# CH32M030C8T7_1V3.net
KiCad netlist of a schematic drawn in Altium Designer
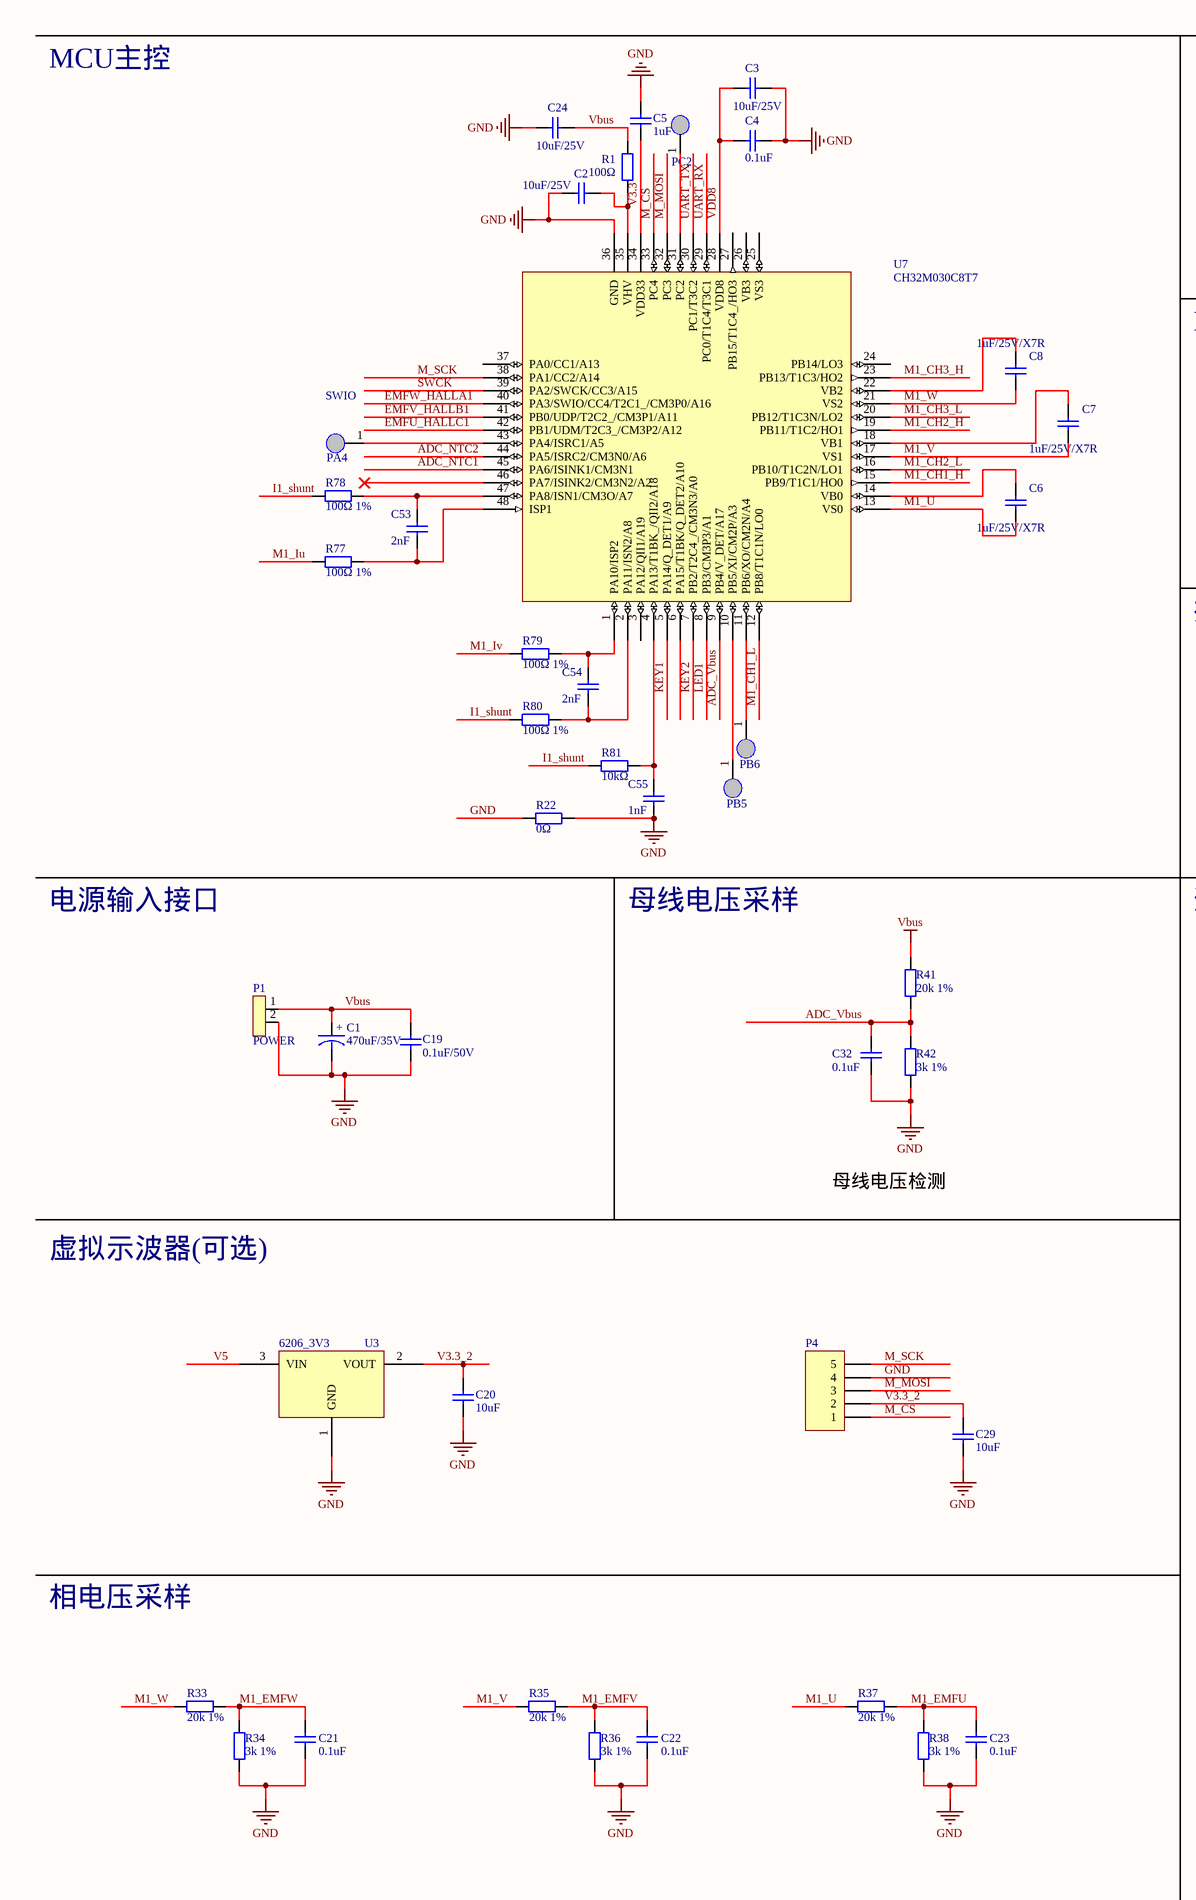
[diagram p0: CH32M030C8T7_1V3.SchDoc, left]
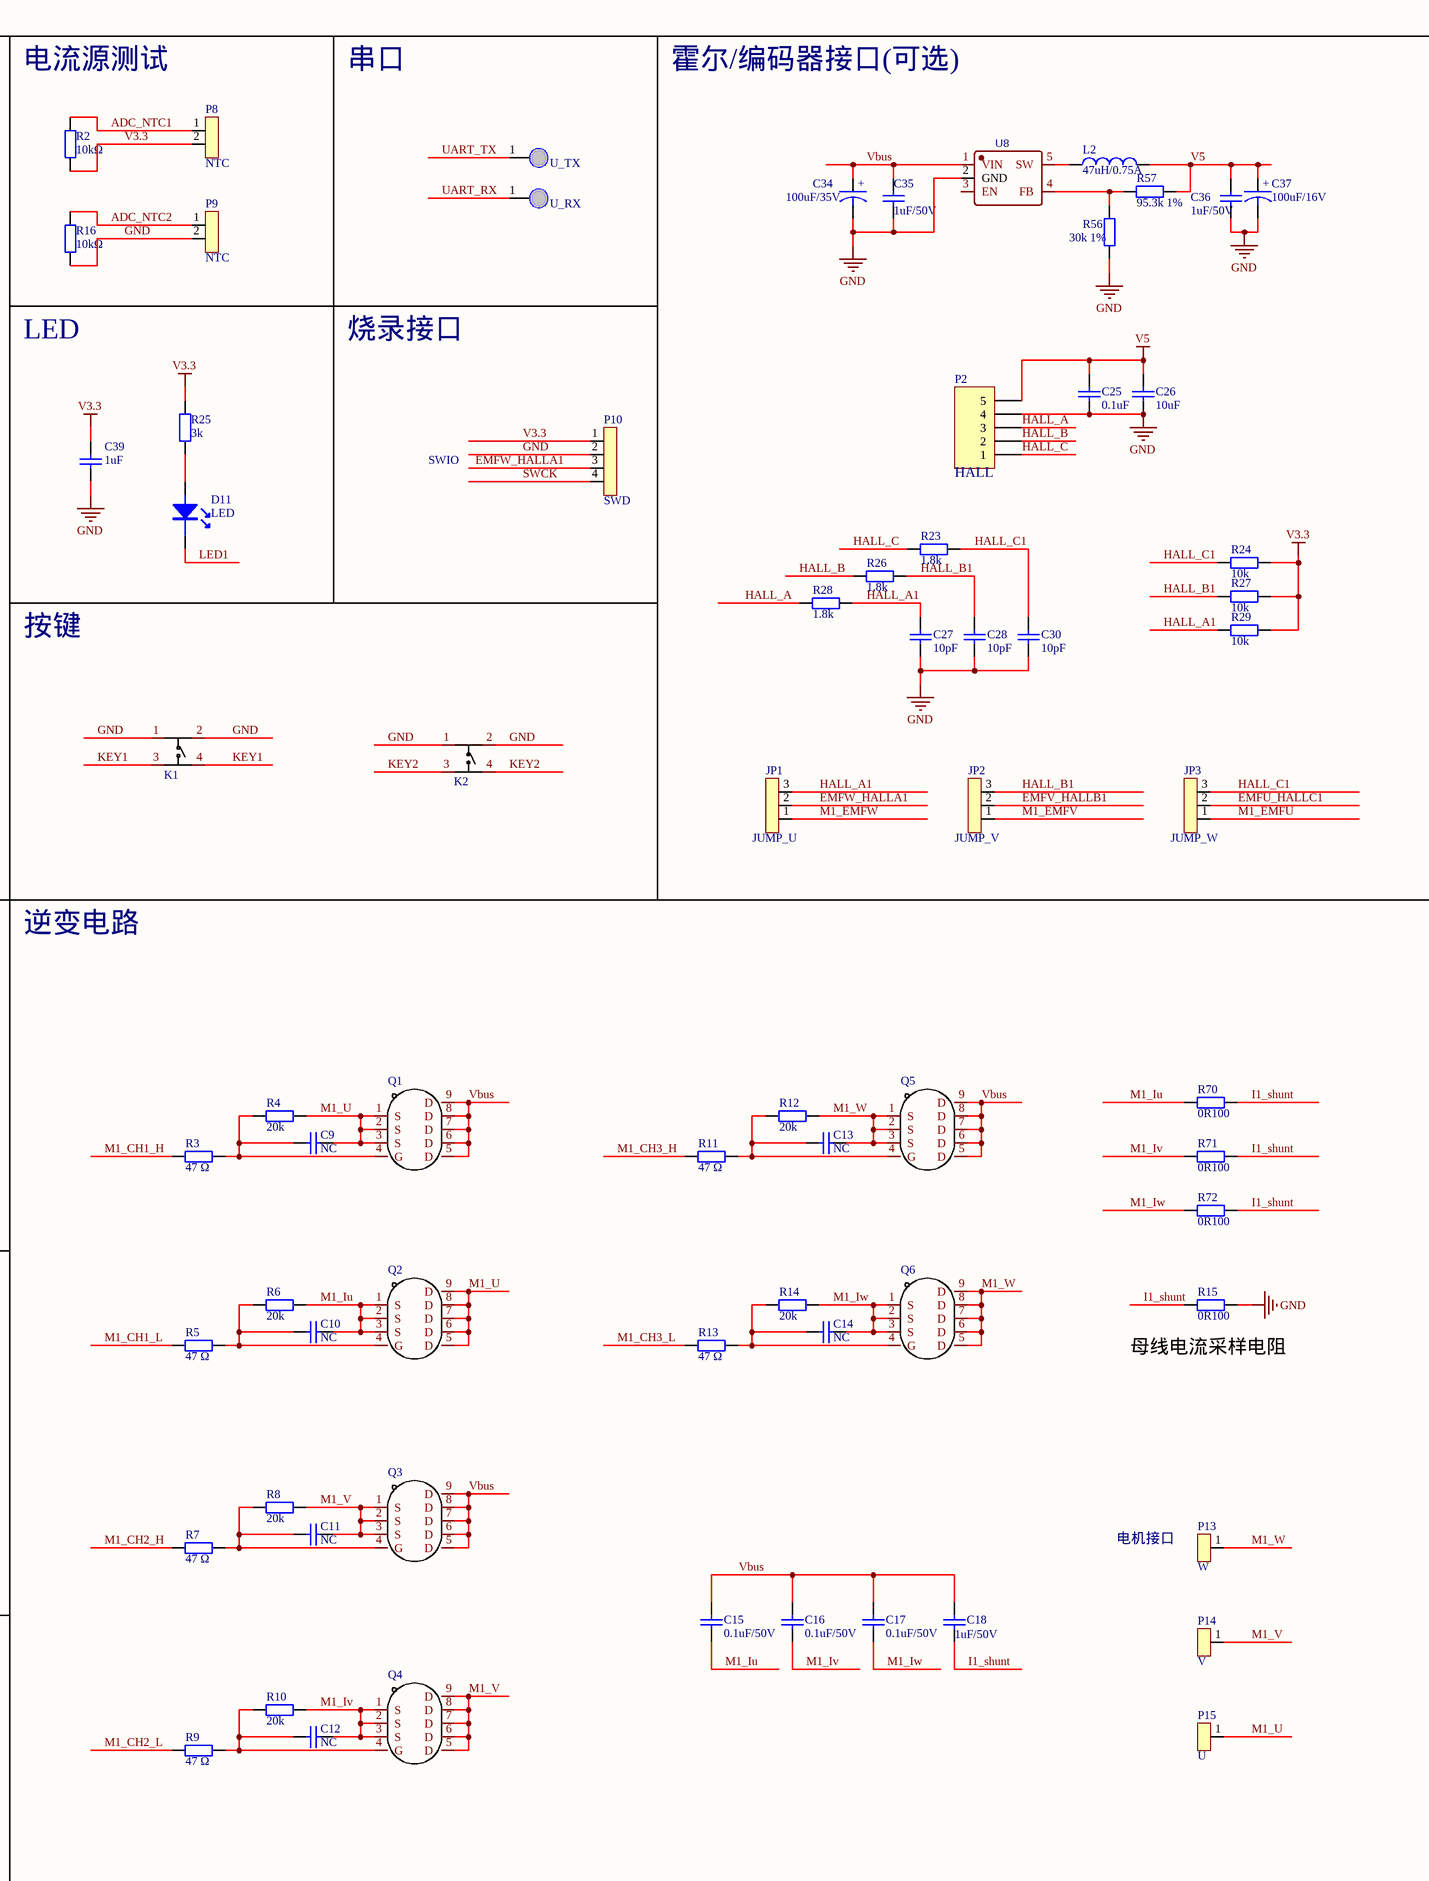
[diagram p1: CH32M030C8T7_1V3.SchDoc, right]

(export (version "E")
  (design (tool "Eeschema 10.0.6"))
  (components
    (comp (ref "C1")
      (value "470uF/35V")
      (footprint "M_C_RB_D10F5")
      (description "Capacitor")
      (libsource (lib "SMARTCORTEX M3-1700_1") (part "CAPACITOR POL_2"))
    )
    (comp (ref "C2")
      (value "10uF/25V")
      (footprint "M_C0805-")
      (description "Capacitor (Semiconductor SIM Model)")
      (libsource (lib "Miscellaneous Devices") (part "Cap Semi"))
    )
    (comp (ref "C3")
      (value "10uF/25V")
      (footprint "M_C0805-")
      (description "Capacitor (Semiconductor SIM Model)")
      (libsource (lib "Miscellaneous Devices") (part "Cap Semi"))
    )
    (comp (ref "C4")
      (value "0.1uF")
      (footprint "M_C0402-")
      (description "Capacitor (Semiconductor SIM Model)")
      (libsource (lib "Miscellaneous Devices") (part "Cap Semi"))
    )
    (comp (ref "C5")
      (value "1uF")
      (footprint "M_C0603")
      (description "Capacitor (Semiconductor SIM Model)")
      (libsource (lib "Miscellaneous Devices") (part "Cap Semi"))
    )
    (comp (ref "C6")
      (value "1uF/25V/X7R")
      (footprint "M_C0805")
      (description "Capacitor (Semiconductor SIM Model)")
      (libsource (lib "Miscellaneous Devices") (part "Cap Semi"))
    )
    (comp (ref "C7")
      (value "1uF/25V/X7R")
      (footprint "M_C0805")
      (description "Capacitor (Semiconductor SIM Model)")
      (libsource (lib "Miscellaneous Devices") (part "Cap Semi"))
    )
    (comp (ref "C8")
      (value "1uF/25V/X7R")
      (footprint "M_C0805")
      (description "Capacitor (Semiconductor SIM Model)")
      (libsource (lib "Miscellaneous Devices") (part "Cap Semi"))
    )
    (comp (ref "C9")
      (value "NC")
      (footprint "M_C0402-")
      (description "Capacitor (Semiconductor SIM Model)")
      (libsource (lib "Miscellaneous Devices") (part "Cap Semi"))
    )
    (comp (ref "C10")
      (value "NC")
      (footprint "M_C0402-")
      (description "Capacitor (Semiconductor SIM Model)")
      (libsource (lib "Miscellaneous Devices") (part "Cap Semi"))
    )
    (comp (ref "C11")
      (value "NC")
      (footprint "M_C0402-")
      (description "Capacitor (Semiconductor SIM Model)")
      (libsource (lib "Miscellaneous Devices") (part "Cap Semi"))
    )
    (comp (ref "C12")
      (value "NC")
      (footprint "M_C0402-")
      (description "Capacitor (Semiconductor SIM Model)")
      (libsource (lib "Miscellaneous Devices") (part "Cap Semi"))
    )
    (comp (ref "C13")
      (value "NC")
      (footprint "M_C0402-")
      (description "Capacitor (Semiconductor SIM Model)")
      (libsource (lib "Miscellaneous Devices") (part "Cap Semi"))
    )
    (comp (ref "C14")
      (value "NC")
      (footprint "M_C0402-")
      (description "Capacitor (Semiconductor SIM Model)")
      (libsource (lib "Miscellaneous Devices") (part "Cap Semi"))
    )
    (comp (ref "C15")
      (value "0.1uF/50V")
      (footprint "M_C0402-")
      (description "Capacitor (Semiconductor SIM Model)")
      (libsource (lib "Miscellaneous Devices") (part "Cap Semi"))
    )
    (comp (ref "C16")
      (value "0.1uF/50V")
      (footprint "M_C0402-")
      (description "Capacitor (Semiconductor SIM Model)")
      (libsource (lib "Miscellaneous Devices") (part "Cap Semi"))
    )
    (comp (ref "C17")
      (value "0.1uF/50V")
      (footprint "M_C0402-")
      (description "Capacitor (Semiconductor SIM Model)")
      (libsource (lib "Miscellaneous Devices") (part "Cap Semi"))
    )
    (comp (ref "C18")
      (value "1uF/50V")
      (footprint "M_C0805-")
      (description "Capacitor (Semiconductor SIM Model)")
      (libsource (lib "Miscellaneous Devices") (part "Cap Semi"))
    )
    (comp (ref "C19")
      (value "0.1uF/50V")
      (footprint "M_C0402-")
      (description "Capacitor (Semiconductor SIM Model)")
      (libsource (lib "Miscellaneous Devices") (part "Cap Semi"))
    )
    (comp (ref "C20")
      (value "10uF")
      (footprint "M_C0603")
      (description "Capacitor (Semiconductor SIM Model)")
      (libsource (lib "Miscellaneous Devices") (part "Cap Semi"))
    )
    (comp (ref "C21")
      (value "0.1uF")
      (footprint "M_C0402-")
      (description "Capacitor (Semiconductor SIM Model)")
      (libsource (lib "Miscellaneous Devices") (part "Cap Semi"))
    )
    (comp (ref "C22")
      (value "0.1uF")
      (footprint "M_C0402-")
      (description "Capacitor (Semiconductor SIM Model)")
      (libsource (lib "Miscellaneous Devices") (part "Cap Semi"))
    )
    (comp (ref "C23")
      (value "0.1uF")
      (footprint "M_C0402-")
      (description "Capacitor (Semiconductor SIM Model)")
      (libsource (lib "Miscellaneous Devices") (part "Cap Semi"))
    )
    (comp (ref "C24")
      (value "10uF/25V")
      (footprint "M_C0805-")
      (description "Capacitor (Semiconductor SIM Model)")
      (libsource (lib "Miscellaneous Devices") (part "Cap Semi"))
    )
    (comp (ref "C25")
      (value "0.1uF")
      (footprint "0603")
      (description "Capacitor (Semiconductor SIM Model)")
      (libsource (lib "Miscellaneous Devices") (part "Cap Semi"))
    )
    (comp (ref "C26")
      (value "10uF")
      (footprint "0603")
      (description "Capacitor (Semiconductor SIM Model)")
      (libsource (lib "Miscellaneous Devices") (part "Cap Semi"))
    )
    (comp (ref "C27")
      (value "10pF")
      (footprint "0603")
      (description "Capacitor (Semiconductor SIM Model)")
      (libsource (lib "Miscellaneous Devices") (part "Cap Semi"))
    )
    (comp (ref "C28")
      (value "10pF")
      (footprint "0603")
      (description "Capacitor (Semiconductor SIM Model)")
      (libsource (lib "Miscellaneous Devices") (part "Cap Semi"))
    )
    (comp (ref "C29")
      (value "10uF")
      (footprint "M_C0603")
      (description "Capacitor (Semiconductor SIM Model)")
      (libsource (lib "Miscellaneous Devices") (part "Cap Semi"))
    )
    (comp (ref "C30")
      (value "10pF")
      (footprint "0603")
      (description "Capacitor (Semiconductor SIM Model)")
      (libsource (lib "Miscellaneous Devices") (part "Cap Semi"))
    )
    (comp (ref "C32")
      (value "0.1uF")
      (footprint "M_C0402-")
      (description "Capacitor (Semiconductor SIM Model)")
      (libsource (lib "Miscellaneous Devices") (part "Cap Semi"))
    )
    (comp (ref "C34")
      (value "100uF/35V")
      (footprint "M_C_RB4/2_D6.3")
      (description "Capacitor")
      (libsource (lib "SMARTCORTEX M3-1700_1") (part "CAPACITOR POL_2"))
    )
    (comp (ref "C35")
      (value "1uF/50V")
      (footprint "M_C0603")
      (description "Capacitor (Semiconductor SIM Model)")
      (libsource (lib "Miscellaneous Devices") (part "Cap Semi"))
    )
    (comp (ref "C36")
      (value "1uF/50V")
      (footprint "M_C0603")
      (description "Capacitor (Semiconductor SIM Model)")
      (libsource (lib "Miscellaneous Devices") (part "Cap Semi"))
    )
    (comp (ref "C37")
      (value "100uF/16V")
      (footprint "M_C_RB4/2_D6.3")
      (description "Capacitor")
      (libsource (lib "SMARTCORTEX M3-1700_1") (part "CAPACITOR POL_2"))
    )
    (comp (ref "C39")
      (value "1uF")
      (footprint "M_C0603")
      (description "Capacitor (Semiconductor SIM Model)")
      (libsource (lib "Miscellaneous Devices") (part "Cap Semi"))
    )
    (comp (ref "C53")
      (value "2nF")
      (footprint "M_C0402-")
      (description "Capacitor (Semiconductor SIM Model)")
      (libsource (lib "Miscellaneous Devices") (part "Cap Semi"))
    )
    (comp (ref "C54")
      (value "2nF")
      (footprint "M_C0402-")
      (description "Capacitor (Semiconductor SIM Model)")
      (libsource (lib "Miscellaneous Devices") (part "Cap Semi"))
    )
    (comp (ref "C55")
      (value "1nF")
      (footprint "M_C0402-")
      (description "Capacitor (Semiconductor SIM Model)")
      (libsource (lib "Miscellaneous Devices") (part "Cap Semi"))
    )
    (comp (ref "D11") (value "LED") (footprint "LED-0603") (libsource (lib "SUNWIN_SCH") (part "LED")))
    (comp (ref "JP1") (value "JUMP_U") (footprint "M_JUMP-3") (libsource (lib "SUNWIN_SCH") (part "3PIN")))
    (comp (ref "JP2") (value "JUMP_V") (footprint "M_JUMP-3") (libsource (lib "SUNWIN_SCH") (part "3PIN")))
    (comp (ref "JP3") (value "JUMP_W") (footprint "M_JUMP-3") (libsource (lib "SUNWIN_SCH") (part "3PIN")))
    (comp (ref "K1")
      (value "KH-6X6X8H-STM")
      (footprint "KEY2-SMD")
      (libsource (lib "altium-import") (part "root_0_KH-6X6X8H-STM_"))
    )
    (comp (ref "K2")
      (value "KH-6X6X8H-STM")
      (footprint "KEY2-SMD")
      (libsource (lib "altium-import") (part "root_0_KH-6X6X8H-STM_"))
    )
    (comp (ref "L2")
      (value "47uH")
      (footprint "SMD4030")
      (fields (field (name "ALTIUM_UNNAMED_1") "47uH/0.75A"))
      (libsource (lib "SUNWIN_SCH") (part "INDUCTOR"))
    )
    (comp (ref "P1") (value "POWER") (footprint "WJ15EDGRC3.81-2") (libsource (lib "") (part "2PIN_1")))
    (comp (ref "P2")
      (value "Header 5")
      (footprint "2510-5")
      (description "Header, 5-Pin")
      (libsource (lib "Miscellaneous Connectors") (part "Header 5"))
    )
    (comp (ref "P4")
      (value "HEADER 5")
      (footprint "HDR2.54-LI-5P")
      (description "Header, 5-Pin")
      (libsource (lib "wch_sch_others") (part "HEADER 5"))
    )
    (comp (ref "P8") (value "NTC") (footprint "GH1.25-2P") (libsource (lib "SUNWIN_SCH") (part "2PIN")))
    (comp (ref "P9") (value "NTC") (footprint "GH1.25-2P") (libsource (lib "SUNWIN_SCH") (part "2PIN")))
    (comp (ref "P10") (value "SWD") (footprint "HDR2.54-LI-4P") (libsource (lib "SUNWIN_SCH") (part "4PIN")))
    (comp (ref "P13")
      (value "W")
      (footprint "M_PAD-2.4/3.7")
      (description "CONNECTOR")
      (libsource (lib "SUNWIN_SCH") (part "1PIN"))
    )
    (comp (ref "P14")
      (value "V")
      (footprint "M_PAD-2.4/3.7")
      (description "CONNECTOR")
      (libsource (lib "SUNWIN_SCH") (part "1PIN"))
    )
    (comp (ref "P15")
      (value "U")
      (footprint "M_PAD-2.4/3.7")
      (description "CONNECTOR")
      (libsource (lib "SUNWIN_SCH") (part "1PIN"))
    )
    (comp (ref "PA4")
      (value "Testpoint")
      (footprint "TEST-1.2")
      (description "测试点")
      (libsource (lib "wch_sch_others") (part "Testpoint"))
    )
    (comp (ref "PB5")
      (value "Testpoint")
      (footprint "TEST-1.2")
      (description "测试点")
      (libsource (lib "wch_sch_others") (part "Testpoint"))
    )
    (comp (ref "PB6")
      (value "Testpoint")
      (footprint "TEST-1.2")
      (description "测试点")
      (libsource (lib "wch_sch_others") (part "Testpoint"))
    )
    (comp (ref "PC2")
      (value "Testpoint")
      (footprint "TEST-1.2")
      (description "测试点")
      (libsource (lib "wch_sch_others") (part "Testpoint"))
    )
    (comp (ref "Q1")
      (value "~")
      (footprint "M_PDFN-8_L5.8-W4.9")
      (fields (field (name "MANUFACTURER PART") "NP100N03D6"))
      (libsource (lib "altium-import") (part "root_0_NP100N03D6_"))
    )
    (comp (ref "Q2")
      (value "~")
      (footprint "M_PDFN-8_L5.8-W4.9")
      (fields (field (name "MANUFACTURER PART") "NP100N03D6"))
      (libsource (lib "altium-import") (part "root_0_NP100N03D6_"))
    )
    (comp (ref "Q3")
      (value "~")
      (footprint "M_PDFN-8_L5.8-W4.9")
      (fields (field (name "MANUFACTURER PART") "NP100N03D6"))
      (libsource (lib "altium-import") (part "root_0_NP100N03D6_"))
    )
    (comp (ref "Q4")
      (value "~")
      (footprint "M_PDFN-8_L5.8-W4.9")
      (fields (field (name "MANUFACTURER PART") "NP100N03D6"))
      (libsource (lib "altium-import") (part "root_0_NP100N03D6_"))
    )
    (comp (ref "Q5")
      (value "~")
      (footprint "M_PDFN-8_L5.8-W4.9")
      (fields (field (name "MANUFACTURER PART") "NP100N03D6"))
      (libsource (lib "altium-import") (part "root_0_NP100N03D6_"))
    )
    (comp (ref "Q6")
      (value "~")
      (footprint "M_PDFN-8_L5.8-W4.9")
      (fields (field (name "MANUFACTURER PART") "NP100N03D6"))
      (libsource (lib "altium-import") (part "root_0_NP100N03D6_"))
    )
    (comp (ref "R1")
      (value "100Ω")
      (footprint "M_R1206-")
      (description "Resistor")
      (libsource (lib "") (part "Res2_2"))
    )
    (comp (ref "R2")
      (value "10kΩ")
      (footprint "M_R0402-")
      (description "Resistor")
      (libsource (lib "") (part "Res2_2"))
    )
    (comp (ref "R3")
      (value "47 Ω")
      (footprint "M_R0402-")
      (description "Resistor")
      (libsource (lib "") (part "Res2_1"))
    )
    (comp (ref "R4")
      (value "20k")
      (footprint "M_R0402-")
      (description "Resistor")
      (libsource (lib "") (part "Res2_1"))
    )
    (comp (ref "R5")
      (value "47 Ω")
      (footprint "M_R0402-")
      (description "Resistor")
      (libsource (lib "") (part "Res2_1"))
    )
    (comp (ref "R6")
      (value "20k")
      (footprint "M_R0402-")
      (description "Resistor")
      (libsource (lib "") (part "Res2_1"))
    )
    (comp (ref "R7")
      (value "47 Ω")
      (footprint "M_R0402-")
      (description "Resistor")
      (libsource (lib "") (part "Res2_1"))
    )
    (comp (ref "R8")
      (value "20k")
      (footprint "M_R0402-")
      (description "Resistor")
      (libsource (lib "") (part "Res2_1"))
    )
    (comp (ref "R9")
      (value "47 Ω")
      (footprint "M_R0402-")
      (description "Resistor")
      (libsource (lib "") (part "Res2_1"))
    )
    (comp (ref "R10")
      (value "20k")
      (footprint "M_R0402-")
      (description "Resistor")
      (libsource (lib "") (part "Res2_1"))
    )
    (comp (ref "R11")
      (value "47 Ω")
      (footprint "M_R0402-")
      (description "Resistor")
      (libsource (lib "") (part "Res2_1"))
    )
    (comp (ref "R12")
      (value "20k")
      (footprint "M_R0402-")
      (description "Resistor")
      (libsource (lib "") (part "Res2_1"))
    )
    (comp (ref "R13")
      (value "47 Ω")
      (footprint "M_R0402-")
      (description "Resistor")
      (libsource (lib "") (part "Res2_1"))
    )
    (comp (ref "R14")
      (value "20k")
      (footprint "M_R0402-")
      (description "Resistor")
      (libsource (lib "") (part "Res2_1"))
    )
    (comp (ref "R15")
      (value "0R100")
      (footprint "M_R2512")
      (description "Resistor")
      (libsource (lib "") (part "Res2_1"))
    )
    (comp (ref "R16")
      (value "10kΩ")
      (footprint "M_R0402-")
      (description "Resistor")
      (libsource (lib "") (part "Res2_2"))
    )
    (comp (ref "R22")
      (value "0Ω")
      (footprint "M_R0402-")
      (description "Resistor")
      (libsource (lib "Miscellaneous Devices") (part "Res2"))
    )
    (comp (ref "R23")
      (value "1.8k")
      (footprint "0603")
      (description "Resistor")
      (libsource (lib "Miscellaneous Devices") (part "Res2"))
    )
    (comp (ref "R24")
      (value "10k")
      (footprint "M_R0402-")
      (description "Resistor")
      (libsource (lib "") (part "Res2_1"))
    )
    (comp (ref "R25")
      (value "3k")
      (footprint "M_R0402-")
      (description "Resistor")
      (libsource (lib "") (part "Res2_2"))
    )
    (comp (ref "R26")
      (value "1.8k")
      (footprint "0603")
      (description "Resistor")
      (libsource (lib "Miscellaneous Devices") (part "Res2"))
    )
    (comp (ref "R27")
      (value "10k")
      (footprint "M_R0402-")
      (description "Resistor")
      (libsource (lib "") (part "Res2_1"))
    )
    (comp (ref "R28")
      (value "1.8k")
      (footprint "0603")
      (description "Resistor")
      (libsource (lib "Miscellaneous Devices") (part "Res2"))
    )
    (comp (ref "R29")
      (value "10k")
      (footprint "M_R0402-")
      (description "Resistor")
      (libsource (lib "") (part "Res2_1"))
    )
    (comp (ref "R33")
      (value "20k 1%")
      (footprint "M_R0603")
      (description "Resistor")
      (libsource (lib "") (part "Res2_1"))
    )
    (comp (ref "R34")
      (value "3k 1%")
      (footprint "M_R0402-")
      (description "Resistor")
      (libsource (lib "") (part "Res2_2"))
    )
    (comp (ref "R35")
      (value "20k 1%")
      (footprint "M_R0603")
      (description "Resistor")
      (libsource (lib "") (part "Res2_1"))
    )
    (comp (ref "R36")
      (value "3k 1%")
      (footprint "M_R0402-")
      (description "Resistor")
      (libsource (lib "") (part "Res2_2"))
    )
    (comp (ref "R37")
      (value "20k 1%")
      (footprint "M_R0603")
      (description "Resistor")
      (libsource (lib "") (part "Res2_1"))
    )
    (comp (ref "R38")
      (value "3k 1%")
      (footprint "M_R0402-")
      (description "Resistor")
      (libsource (lib "") (part "Res2_2"))
    )
    (comp (ref "R41")
      (value "20k 1%")
      (footprint "M_R0603")
      (description "Resistor")
      (libsource (lib "") (part "Res2_2"))
    )
    (comp (ref "R42")
      (value "3k 1%")
      (footprint "M_R0402-")
      (description "Resistor")
      (libsource (lib "") (part "Res2_2"))
    )
    (comp (ref "R56")
      (value "30k 1%")
      (footprint "M_R0402-")
      (description "Resistor")
      (libsource (lib "") (part "Res2_2"))
    )
    (comp (ref "R57")
      (value "95.3k 1%")
      (footprint "M_R0402-")
      (description "Resistor")
      (libsource (lib "Miscellaneous Devices") (part "Res2"))
    )
    (comp (ref "R70")
      (value "0R100")
      (footprint "M_R2512")
      (description "Resistor")
      (libsource (lib "") (part "Res2_1"))
    )
    (comp (ref "R71")
      (value "0R100")
      (footprint "M_R2512")
      (description "Resistor")
      (libsource (lib "") (part "Res2_1"))
    )
    (comp (ref "R72")
      (value "0R100")
      (footprint "M_R2512")
      (description "Resistor")
      (libsource (lib "") (part "Res2_1"))
    )
    (comp (ref "R77")
      (value "100Ω 1%")
      (footprint "M_R0402-")
      (description "Resistor")
      (libsource (lib "Miscellaneous Devices") (part "Res2"))
    )
    (comp (ref "R78")
      (value "100Ω 1%")
      (footprint "M_R0402-")
      (description "Resistor")
      (libsource (lib "Miscellaneous Devices") (part "Res2"))
    )
    (comp (ref "R79")
      (value "100Ω 1%")
      (footprint "M_R0402-")
      (description "Resistor")
      (libsource (lib "Miscellaneous Devices") (part "Res2"))
    )
    (comp (ref "R80")
      (value "100Ω 1%")
      (footprint "M_R0402-")
      (description "Resistor")
      (libsource (lib "Miscellaneous Devices") (part "Res2"))
    )
    (comp (ref "R81")
      (value "10kΩ")
      (footprint "M_R0402-")
      (description "Resistor")
      (libsource (lib "Miscellaneous Devices") (part "Res2"))
    )
    (comp (ref "U3") (value "6206_3V3") (footprint "SOT-23") (libsource (lib "*") (part "LM1117_3.3V")))
    (comp (ref "U7")
      (value "CH32M030C8T7")
      (footprint "LQFP48")
      (description "RISC-V MCU, 72MHz, USB, Type-C/PD, OPA, CMP, 28V gate driver")
      (libsource (lib "DHXXXSCH") (part "CH32M030C8T7"))
    )
    (comp (ref "U8")
      (value "~")
      (footprint "SOT23-5")
      (fields
        (field (name "BOM_SUPPLIER PART") "C2930954")
        (field (name "BOM_MANUFACTURER PART") "AP2900TB-A1")
      )
      (libsource (lib "altium-import") (part "root_0_AP2900TB-A1_"))
    )
    (comp (ref "U_RX")
      (value "Testpoint")
      (footprint "TEST-1.2")
      (description "测试点")
      (libsource (lib "wch_sch_others") (part "Testpoint"))
    )
    (comp (ref "U_TX")
      (value "Testpoint")
      (footprint "TEST-1.2")
      (description "测试点")
      (libsource (lib "wch_sch_others") (part "Testpoint"))
    )
  )
  (nets
    (net (code "1") (name "/ADC_NTC1") (class "Default")
      (node (ref "P8") (pin "1") (pintype "passive"))
      (node (ref "R2") (pin "2") (pinfunction "2_2") (pintype "passive"))
      (node (ref "U7") (pin "45") (pinfunction "PA6/ISINK1/CM3N1_45") (pintype "bidirectional"))
    )
    (net (code "2") (name "/ADC_NTC2") (class "Default")
      (node (ref "P9") (pin "1") (pintype "passive"))
      (node (ref "R16") (pin "2") (pinfunction "2_2") (pintype "passive"))
      (node (ref "U7") (pin "44") (pinfunction "PA5/ISRC2/CM3N0/A6_44") (pintype "bidirectional"))
    )
    (net (code "3") (name "/ADC_Vbus") (class "Default")
      (node (ref "C32") (pin "1") (pinfunction "1_1") (pintype "passive"))
      (node (ref "R41") (pin "1") (pinfunction "1_1") (pintype "passive"))
      (node (ref "R42") (pin "2") (pinfunction "2_2") (pintype "passive"))
      (node (ref "U7") (pin "9") (pinfunction "PB4/V_DET/A17_9") (pintype "bidirectional"))
    )
    (net (code "4") (name "/EMFU_HALLC1") (class "Default")
      (node (ref "JP3") (pin "2") (pintype "passive"))
      (node (ref "U7") (pin "42") (pinfunction "PB1/UDM/T2C3_/CM3P2/A12_42") (pintype "bidirectional"))
    )
    (net (code "5") (name "/EMFV_HALLB1") (class "Default")
      (node (ref "JP2") (pin "2") (pintype "passive"))
      (node (ref "U7") (pin "41") (pinfunction "PB0/UDP/T2C2_/CM3P1/A11_41") (pintype "bidirectional"))
    )
    (net (code "6") (name "/EMFW_HALLA1") (class "Default")
      (node (ref "JP1") (pin "2") (pintype "passive"))
      (node (ref "P10") (pin "3") (pintype "passive"))
      (node (ref "U7") (pin "40") (pinfunction "PA3/SWIO/CC4/T2C1_/CM3P0/A16_40") (pintype "bidirectional"))
    )
    (net (code "7") (name "/HALL_A") (class "Default")
      (node (ref "P2") (pin "3") (pinfunction "3_3") (pintype "passive"))
      (node (ref "R28") (pin "1") (pinfunction "1_1") (pintype "passive"))
    )
    (net (code "8") (name "/HALL_A1") (class "Default")
      (node (ref "C27") (pin "1") (pinfunction "1_1") (pintype "passive"))
      (node (ref "JP1") (pin "3") (pintype "passive"))
      (node (ref "R28") (pin "2") (pinfunction "2_2") (pintype "passive"))
      (node (ref "R29") (pin "2") (pinfunction "2_2") (pintype "passive"))
    )
    (net (code "9") (name "/HALL_B") (class "Default")
      (node (ref "P2") (pin "2") (pinfunction "2_2") (pintype "passive"))
      (node (ref "R26") (pin "1") (pinfunction "1_1") (pintype "passive"))
    )
    (net (code "10") (name "/HALL_B1") (class "Default")
      (node (ref "C28") (pin "1") (pinfunction "1_1") (pintype "passive"))
      (node (ref "JP2") (pin "3") (pintype "passive"))
      (node (ref "R26") (pin "2") (pinfunction "2_2") (pintype "passive"))
      (node (ref "R27") (pin "2") (pinfunction "2_2") (pintype "passive"))
    )
    (net (code "11") (name "/HALL_C") (class "Default")
      (node (ref "P2") (pin "1") (pinfunction "1_1") (pintype "passive"))
      (node (ref "R23") (pin "1") (pinfunction "1_1") (pintype "passive"))
    )
    (net (code "12") (name "/HALL_C1") (class "Default")
      (node (ref "C30") (pin "1") (pinfunction "1_1") (pintype "passive"))
      (node (ref "JP3") (pin "3") (pintype "passive"))
      (node (ref "R23") (pin "2") (pinfunction "2_2") (pintype "passive"))
      (node (ref "R24") (pin "2") (pinfunction "2_2") (pintype "passive"))
    )
    (net (code "13") (name "/I1_shunt") (class "Default")
      (node (ref "C18") (pin "2") (pinfunction "2_2") (pintype "passive"))
      (node (ref "R15") (pin "2") (pinfunction "2_2") (pintype "passive"))
      (node (ref "R70") (pin "1") (pinfunction "1_1") (pintype "passive"))
      (node (ref "R71") (pin "1") (pinfunction "1_1") (pintype "passive"))
      (node (ref "R72") (pin "1") (pinfunction "1_1") (pintype "passive"))
      (node (ref "R78") (pin "1") (pinfunction "1_1") (pintype "passive"))
      (node (ref "R80") (pin "1") (pinfunction "1_1") (pintype "passive"))
      (node (ref "R81") (pin "1") (pinfunction "1_1") (pintype "passive"))
    )
    (net (code "14") (name "/KEY1") (class "Default")
      (node (ref "K1") (pin "3") (pinfunction "C_3") (pintype "passive"))
      (node (ref "K1") (pin "4") (pinfunction "D_4") (pintype "passive"))
      (node (ref "U7") (pin "5") (pinfunction "PA14/Q_DET1/A9_5") (pintype "bidirectional"))
    )
    (net (code "15") (name "/KEY2") (class "Default")
      (node (ref "K2") (pin "3") (pinfunction "C_3") (pintype "passive"))
      (node (ref "K2") (pin "4") (pinfunction "D_4") (pintype "passive"))
      (node (ref "U7") (pin "7") (pinfunction "PB2/T2C4_/CM3N3/A0_7") (pintype "bidirectional"))
    )
    (net (code "16") (name "/LED1") (class "Default")
      (node (ref "D11") (pin "2") (pinfunction "K_2") (pintype "passive"))
      (node (ref "U7") (pin "8") (pinfunction "PB3/CM3P3/A1_8") (pintype "bidirectional"))
    )
    (net (code "17") (name "/M1_CH1_H") (class "Default")
      (node (ref "R3") (pin "2") (pinfunction "2_2") (pintype "passive"))
      (node (ref "U7") (pin "15") (pinfunction "PB9/T1C1/HO0_15") (pintype "output"))
    )
    (net (code "18") (name "/M1_CH1_L") (class "Default")
      (node (ref "R5") (pin "2") (pinfunction "2_2") (pintype "passive"))
      (node (ref "U7") (pin "12") (pinfunction "PB8/T1C1N/LO0_12") (pintype "bidirectional"))
    )
    (net (code "19") (name "/M1_CH2_H") (class "Default")
      (node (ref "R7") (pin "2") (pinfunction "2_2") (pintype "passive"))
      (node (ref "U7") (pin "19") (pinfunction "PB11/T1C2/HO1_19") (pintype "output"))
    )
    (net (code "20") (name "/M1_CH2_L") (class "Default")
      (node (ref "R9") (pin "2") (pinfunction "2_2") (pintype "passive"))
      (node (ref "U7") (pin "16") (pinfunction "PB10/T1C2N/LO1_16") (pintype "bidirectional"))
    )
    (net (code "21") (name "/M1_CH3_H") (class "Default")
      (node (ref "R11") (pin "2") (pinfunction "2_2") (pintype "passive"))
      (node (ref "U7") (pin "23") (pinfunction "PB13/T1C3/HO2_23") (pintype "output"))
    )
    (net (code "22") (name "/M1_CH3_L") (class "Default")
      (node (ref "R13") (pin "2") (pinfunction "2_2") (pintype "passive"))
      (node (ref "U7") (pin "20") (pinfunction "PB12/T1C3N/LO2_20") (pintype "bidirectional"))
    )
    (net (code "23") (name "/M1_EMFU") (class "Default")
      (node (ref "C23") (pin "1") (pinfunction "1_1") (pintype "passive"))
      (node (ref "JP3") (pin "1") (pintype "passive"))
      (node (ref "R37") (pin "1") (pinfunction "1_1") (pintype "passive"))
      (node (ref "R38") (pin "2") (pinfunction "2_2") (pintype "passive"))
    )
    (net (code "24") (name "/M1_EMFV") (class "Default")
      (node (ref "C22") (pin "1") (pinfunction "1_1") (pintype "passive"))
      (node (ref "JP2") (pin "1") (pintype "passive"))
      (node (ref "R35") (pin "1") (pinfunction "1_1") (pintype "passive"))
      (node (ref "R36") (pin "2") (pinfunction "2_2") (pintype "passive"))
    )
    (net (code "25") (name "/M1_EMFW") (class "Default")
      (node (ref "C21") (pin "1") (pinfunction "1_1") (pintype "passive"))
      (node (ref "JP1") (pin "1") (pintype "passive"))
      (node (ref "R33") (pin "1") (pinfunction "1_1") (pintype "passive"))
      (node (ref "R34") (pin "2") (pinfunction "2_2") (pintype "passive"))
    )
    (net (code "26") (name "/M1_Iu") (class "Default")
      (node (ref "C10") (pin "2") (pinfunction "2_2") (pintype "passive"))
      (node (ref "C15") (pin "2") (pinfunction "2_2") (pintype "passive"))
      (node (ref "Q2") (pin "1") (pinfunction "S_1") (pintype "passive"))
      (node (ref "Q2") (pin "2") (pinfunction "S_2") (pintype "passive"))
      (node (ref "Q2") (pin "3") (pinfunction "S_3") (pintype "passive"))
      (node (ref "R6") (pin "1") (pinfunction "1_1") (pintype "passive"))
      (node (ref "R70") (pin "2") (pinfunction "2_2") (pintype "passive"))
      (node (ref "R77") (pin "1") (pinfunction "1_1") (pintype "passive"))
    )
    (net (code "27") (name "/M1_Iv") (class "Default")
      (node (ref "C12") (pin "2") (pinfunction "2_2") (pintype "passive"))
      (node (ref "C16") (pin "2") (pinfunction "2_2") (pintype "passive"))
      (node (ref "Q4") (pin "1") (pinfunction "S_1") (pintype "passive"))
      (node (ref "Q4") (pin "2") (pinfunction "S_2") (pintype "passive"))
      (node (ref "Q4") (pin "3") (pinfunction "S_3") (pintype "passive"))
      (node (ref "R10") (pin "1") (pinfunction "1_1") (pintype "passive"))
      (node (ref "R71") (pin "2") (pinfunction "2_2") (pintype "passive"))
      (node (ref "R79") (pin "1") (pinfunction "1_1") (pintype "passive"))
    )
    (net (code "28") (name "/M1_Iw") (class "Default")
      (node (ref "C14") (pin "2") (pinfunction "2_2") (pintype "passive"))
      (node (ref "C17") (pin "2") (pinfunction "2_2") (pintype "passive"))
      (node (ref "Q6") (pin "1") (pinfunction "S_1") (pintype "passive"))
      (node (ref "Q6") (pin "2") (pinfunction "S_2") (pintype "passive"))
      (node (ref "Q6") (pin "3") (pinfunction "S_3") (pintype "passive"))
      (node (ref "R14") (pin "1") (pinfunction "1_1") (pintype "passive"))
      (node (ref "R72") (pin "2") (pinfunction "2_2") (pintype "passive"))
    )
    (net (code "29") (name "/M1_U") (class "Default")
      (node (ref "C6") (pin "2") (pinfunction "2_2") (pintype "passive"))
      (node (ref "C9") (pin "2") (pinfunction "2_2") (pintype "passive"))
      (node (ref "P15") (pin "1") (pintype "passive"))
      (node (ref "Q1") (pin "1") (pinfunction "S_1") (pintype "passive"))
      (node (ref "Q1") (pin "2") (pinfunction "S_2") (pintype "passive"))
      (node (ref "Q1") (pin "3") (pinfunction "S_3") (pintype "passive"))
      (node (ref "Q2") (pin "5") (pinfunction "D_5") (pintype "passive"))
      (node (ref "Q2") (pin "6") (pinfunction "D_6") (pintype "passive"))
      (node (ref "Q2") (pin "7") (pinfunction "D_7") (pintype "passive"))
      (node (ref "Q2") (pin "8") (pinfunction "D_8") (pintype "passive"))
      (node (ref "Q2") (pin "9") (pinfunction "D_9") (pintype "passive"))
      (node (ref "R37") (pin "2") (pinfunction "2_2") (pintype "passive"))
      (node (ref "R4") (pin "1") (pinfunction "1_1") (pintype "passive"))
      (node (ref "U7") (pin "13") (pinfunction "VS0_13") (pintype "bidirectional"))
    )
    (net (code "30") (name "/M1_V") (class "Default")
      (node (ref "C11") (pin "2") (pinfunction "2_2") (pintype "passive"))
      (node (ref "C7") (pin "2") (pinfunction "2_2") (pintype "passive"))
      (node (ref "P14") (pin "1") (pintype "passive"))
      (node (ref "Q3") (pin "1") (pinfunction "S_1") (pintype "passive"))
      (node (ref "Q3") (pin "2") (pinfunction "S_2") (pintype "passive"))
      (node (ref "Q3") (pin "3") (pinfunction "S_3") (pintype "passive"))
      (node (ref "Q4") (pin "5") (pinfunction "D_5") (pintype "passive"))
      (node (ref "Q4") (pin "6") (pinfunction "D_6") (pintype "passive"))
      (node (ref "Q4") (pin "7") (pinfunction "D_7") (pintype "passive"))
      (node (ref "Q4") (pin "8") (pinfunction "D_8") (pintype "passive"))
      (node (ref "Q4") (pin "9") (pinfunction "D_9") (pintype "passive"))
      (node (ref "R35") (pin "2") (pinfunction "2_2") (pintype "passive"))
      (node (ref "R8") (pin "1") (pinfunction "1_1") (pintype "passive"))
      (node (ref "U7") (pin "17") (pinfunction "VS1_17") (pintype "bidirectional"))
    )
    (net (code "31") (name "/M1_W") (class "Default")
      (node (ref "C13") (pin "2") (pinfunction "2_2") (pintype "passive"))
      (node (ref "C8") (pin "2") (pinfunction "2_2") (pintype "passive"))
      (node (ref "P13") (pin "1") (pintype "passive"))
      (node (ref "Q5") (pin "1") (pinfunction "S_1") (pintype "passive"))
      (node (ref "Q5") (pin "2") (pinfunction "S_2") (pintype "passive"))
      (node (ref "Q5") (pin "3") (pinfunction "S_3") (pintype "passive"))
      (node (ref "Q6") (pin "5") (pinfunction "D_5") (pintype "passive"))
      (node (ref "Q6") (pin "6") (pinfunction "D_6") (pintype "passive"))
      (node (ref "Q6") (pin "7") (pinfunction "D_7") (pintype "passive"))
      (node (ref "Q6") (pin "8") (pinfunction "D_8") (pintype "passive"))
      (node (ref "Q6") (pin "9") (pinfunction "D_9") (pintype "passive"))
      (node (ref "R12") (pin "1") (pinfunction "1_1") (pintype "passive"))
      (node (ref "R33") (pin "2") (pinfunction "2_2") (pintype "passive"))
      (node (ref "U7") (pin "21") (pinfunction "VS2_21") (pintype "bidirectional"))
    )
    (net (code "32") (name "/M_CS") (class "Default")
      (node (ref "P4") (pin "1") (pinfunction "1_1") (pintype "passive"))
      (node (ref "U7") (pin "33") (pinfunction "PC4_33") (pintype "bidirectional"))
    )
    (net (code "33") (name "/M_MOSI") (class "Default")
      (node (ref "P4") (pin "3") (pinfunction "3_3") (pintype "passive"))
      (node (ref "U7") (pin "32") (pinfunction "PC3_32") (pintype "bidirectional"))
    )
    (net (code "34") (name "/M_SCK") (class "Default")
      (node (ref "P4") (pin "5") (pinfunction "5_5") (pintype "passive"))
      (node (ref "U7") (pin "38") (pinfunction "PA1/CC2/A14_38") (pintype "bidirectional"))
    )
    (net (code "35") (name "/SWCK") (class "Default")
      (node (ref "P10") (pin "4") (pintype "passive"))
      (node (ref "U7") (pin "39") (pinfunction "PA2/SWCK/CC3/A15_39") (pintype "bidirectional"))
    )
    (net (code "36") (name "/UART_RX") (class "Default")
      (node (ref "U7") (pin "29") (pinfunction "PC0/T1C4/T3C1_29") (pintype "bidirectional"))
      (node (ref "U_RX") (pin "1") (pintype "passive"))
    )
    (net (code "37") (name "/UART_TX") (class "Default")
      (node (ref "U7") (pin "30") (pinfunction "PC1/T3C2_30") (pintype "bidirectional"))
      (node (ref "U_TX") (pin "1") (pintype "passive"))
    )
    (net (code "38") (name "/V3.3_2") (class "Default")
      (node (ref "C20") (pin "2") (pinfunction "2_2") (pintype "passive"))
      (node (ref "C29") (pin "1") (pinfunction "1_1") (pintype "passive"))
      (node (ref "P4") (pin "2") (pinfunction "2_2") (pintype "passive"))
      (node (ref "U3") (pin "2") (pinfunction "VOUT_2") (pintype "passive"))
    )
    (net (code "39") (name "/VDD8") (class "Default")
      (node (ref "C3") (pin "2") (pinfunction "2_2") (pintype "passive"))
      (node (ref "C4") (pin "1") (pinfunction "1_1") (pintype "passive"))
      (node (ref "U7") (pin "28") (pinfunction "VDD8_28") (pintype "power_in"))
    )
    (net (code "40") (name "GND") (class "Default")
      (node (ref "C1") (pin "2") (pinfunction "2_2") (pintype "passive"))
      (node (ref "C19") (pin "2") (pinfunction "2_2") (pintype "passive"))
      (node (ref "C2") (pin "1") (pinfunction "1_1") (pintype "passive"))
      (node (ref "C20") (pin "1") (pinfunction "1_1") (pintype "passive"))
      (node (ref "C21") (pin "2") (pinfunction "2_2") (pintype "passive"))
      (node (ref "C22") (pin "2") (pinfunction "2_2") (pintype "passive"))
      (node (ref "C23") (pin "2") (pinfunction "2_2") (pintype "passive"))
      (node (ref "C24") (pin "1") (pinfunction "1_1") (pintype "passive"))
      (node (ref "C25") (pin "2") (pinfunction "2_2") (pintype "passive"))
      (node (ref "C26") (pin "2") (pinfunction "2_2") (pintype "passive"))
      (node (ref "C27") (pin "2") (pinfunction "2_2") (pintype "passive"))
      (node (ref "C28") (pin "2") (pinfunction "2_2") (pintype "passive"))
      (node (ref "C29") (pin "2") (pinfunction "2_2") (pintype "passive"))
      (node (ref "C3") (pin "1") (pinfunction "1_1") (pintype "passive"))
      (node (ref "C30") (pin "2") (pinfunction "2_2") (pintype "passive"))
      (node (ref "C32") (pin "2") (pinfunction "2_2") (pintype "passive"))
      (node (ref "C34") (pin "2") (pinfunction "2_2") (pintype "passive"))
      (node (ref "C35") (pin "2") (pinfunction "2_2") (pintype "passive"))
      (node (ref "C36") (pin "2") (pinfunction "2_2") (pintype "passive"))
      (node (ref "C37") (pin "2") (pinfunction "2_2") (pintype "passive"))
      (node (ref "C39") (pin "2") (pinfunction "2_2") (pintype "passive"))
      (node (ref "C4") (pin "2") (pinfunction "2_2") (pintype "passive"))
      (node (ref "C5") (pin "2") (pinfunction "2_2") (pintype "passive"))
      (node (ref "C55") (pin "2") (pinfunction "2_2") (pintype "passive"))
      (node (ref "K1") (pin "1") (pinfunction "A_1") (pintype "passive"))
      (node (ref "K1") (pin "2") (pinfunction "B_2") (pintype "passive"))
      (node (ref "K2") (pin "1") (pinfunction "A_1") (pintype "passive"))
      (node (ref "K2") (pin "2") (pinfunction "B_2") (pintype "passive"))
      (node (ref "P1") (pin "2") (pintype "passive"))
      (node (ref "P10") (pin "2") (pintype "passive"))
      (node (ref "P2") (pin "4") (pinfunction "4_4") (pintype "passive"))
      (node (ref "P4") (pin "4") (pinfunction "4_4") (pintype "passive"))
      (node (ref "P9") (pin "2") (pintype "passive"))
      (node (ref "R15") (pin "1") (pinfunction "1_1") (pintype "passive"))
      (node (ref "R16") (pin "1") (pinfunction "1_1") (pintype "passive"))
      (node (ref "R22") (pin "1") (pinfunction "1_1") (pintype "passive"))
      (node (ref "R22") (pin "2") (pinfunction "2_2") (pintype "passive"))
      (node (ref "R34") (pin "1") (pinfunction "1_1") (pintype "passive"))
      (node (ref "R36") (pin "1") (pinfunction "1_1") (pintype "passive"))
      (node (ref "R38") (pin "1") (pinfunction "1_1") (pintype "passive"))
      (node (ref "R42") (pin "1") (pinfunction "1_1") (pintype "passive"))
      (node (ref "R56") (pin "1") (pinfunction "1_1") (pintype "passive"))
      (node (ref "U3") (pin "1") (pinfunction "GND_1") (pintype "passive"))
      (node (ref "U7") (pin "36") (pinfunction "GND_36") (pintype "power_in"))
      (node (ref "U8") (pin "2") (pinfunction "GND_2") (pintype "passive"))
    )
    (net (code "41") (name "Net-(D11-A)") (class "Default")
      (node (ref "D11") (pin "1") (pinfunction "A_1") (pintype "passive"))
      (node (ref "R25") (pin "1") (pinfunction "1_1") (pintype "passive"))
    )
    (net (code "42") (name "Net-(Q1-G)") (class "Default")
      (node (ref "C9") (pin "1") (pinfunction "1_1") (pintype "passive"))
      (node (ref "Q1") (pin "4") (pinfunction "G_4") (pintype "passive"))
      (node (ref "R3") (pin "1") (pinfunction "1_1") (pintype "passive"))
      (node (ref "R4") (pin "2") (pinfunction "2_2") (pintype "passive"))
    )
    (net (code "43") (name "Net-(Q2-G)") (class "Default")
      (node (ref "C10") (pin "1") (pinfunction "1_1") (pintype "passive"))
      (node (ref "Q2") (pin "4") (pinfunction "G_4") (pintype "passive"))
      (node (ref "R5") (pin "1") (pinfunction "1_1") (pintype "passive"))
      (node (ref "R6") (pin "2") (pinfunction "2_2") (pintype "passive"))
    )
    (net (code "44") (name "Net-(Q3-G)") (class "Default")
      (node (ref "C11") (pin "1") (pinfunction "1_1") (pintype "passive"))
      (node (ref "Q3") (pin "4") (pinfunction "G_4") (pintype "passive"))
      (node (ref "R7") (pin "1") (pinfunction "1_1") (pintype "passive"))
      (node (ref "R8") (pin "2") (pinfunction "2_2") (pintype "passive"))
    )
    (net (code "45") (name "Net-(Q4-G)") (class "Default")
      (node (ref "C12") (pin "1") (pinfunction "1_1") (pintype "passive"))
      (node (ref "Q4") (pin "4") (pinfunction "G_4") (pintype "passive"))
      (node (ref "R10") (pin "2") (pinfunction "2_2") (pintype "passive"))
      (node (ref "R9") (pin "1") (pinfunction "1_1") (pintype "passive"))
    )
    (net (code "46") (name "Net-(Q5-G)") (class "Default")
      (node (ref "C13") (pin "1") (pinfunction "1_1") (pintype "passive"))
      (node (ref "Q5") (pin "4") (pinfunction "G_4") (pintype "passive"))
      (node (ref "R11") (pin "1") (pinfunction "1_1") (pintype "passive"))
      (node (ref "R12") (pin "2") (pinfunction "2_2") (pintype "passive"))
    )
    (net (code "47") (name "Net-(Q6-G)") (class "Default")
      (node (ref "C14") (pin "1") (pinfunction "1_1") (pintype "passive"))
      (node (ref "Q6") (pin "4") (pinfunction "G_4") (pintype "passive"))
      (node (ref "R13") (pin "1") (pinfunction "1_1") (pintype "passive"))
      (node (ref "R14") (pin "2") (pinfunction "2_2") (pintype "passive"))
    )
    (net (code "48") (name "Net-(U7-ISP1)") (class "Default")
      (node (ref "C53") (pin "2") (pinfunction "2_2") (pintype "passive"))
      (node (ref "R77") (pin "2") (pinfunction "2_2") (pintype "passive"))
      (node (ref "U7") (pin "48") (pinfunction "ISP1_48") (pintype "input"))
    )
    (net (code "49") (name "Net-(U7-PA4{slash}ISRC1{slash}A5)") (class "Default")
      (node (ref "PA4") (pin "1") (pintype "passive"))
      (node (ref "U7") (pin "43") (pinfunction "PA4/ISRC1/A5_43") (pintype "bidirectional"))
    )
    (net (code "50") (name "Net-(U7-PA8{slash}ISN1{slash}CM3O{slash}A7)") (class "Default")
      (node (ref "C53") (pin "1") (pinfunction "1_1") (pintype "passive"))
      (node (ref "R78") (pin "2") (pinfunction "2_2") (pintype "passive"))
      (node (ref "U7") (pin "47") (pinfunction "PA8/ISN1/CM3O/A7_47") (pintype "bidirectional"))
    )
    (net (code "51") (name "Net-(U7-PA10{slash}ISP2)") (class "Default")
      (node (ref "C54") (pin "1") (pinfunction "1_1") (pintype "passive"))
      (node (ref "R79") (pin "2") (pinfunction "2_2") (pintype "passive"))
      (node (ref "U7") (pin "1") (pinfunction "PA10/ISP2_1") (pintype "bidirectional"))
    )
    (net (code "52") (name "Net-(U7-PA11{slash}ISN2{slash}A8)") (class "Default")
      (node (ref "C54") (pin "2") (pinfunction "2_2") (pintype "passive"))
      (node (ref "R80") (pin "2") (pinfunction "2_2") (pintype "passive"))
      (node (ref "U7") (pin "2") (pinfunction "PA11/ISN2/A8_2") (pintype "bidirectional"))
    )
    (net (code "53") (name "Net-(U7-PA13{slash}T1BK_{slash}QII2{slash}A18)") (class "Default")
      (node (ref "C55") (pin "1") (pinfunction "1_1") (pintype "passive"))
      (node (ref "R81") (pin "2") (pinfunction "2_2") (pintype "passive"))
      (node (ref "U7") (pin "4") (pinfunction "PA13/T1BK_/QII2/A18_4") (pintype "bidirectional"))
    )
    (net (code "54") (name "Net-(U7-PB5{slash}XI{slash}CM2P{slash}A3)") (class "Default")
      (node (ref "PB5") (pin "1") (pintype "passive"))
      (node (ref "U7") (pin "10") (pinfunction "PB5/XI/CM2P/A3_10") (pintype "bidirectional"))
    )
    (net (code "55") (name "Net-(U7-PB6{slash}XO{slash}CM2N{slash}A4)") (class "Default")
      (node (ref "PB6") (pin "1") (pintype "passive"))
      (node (ref "U7") (pin "11") (pinfunction "PB6/XO/CM2N/A4_11") (pintype "bidirectional"))
    )
    (net (code "56") (name "Net-(U7-PC2)") (class "Default")
      (node (ref "PC2") (pin "1") (pintype "passive"))
      (node (ref "U7") (pin "31") (pinfunction "PC2_31") (pintype "bidirectional"))
    )
    (net (code "57") (name "Net-(U7-VB0)") (class "Default")
      (node (ref "C6") (pin "1") (pinfunction "1_1") (pintype "passive"))
      (node (ref "U7") (pin "14") (pinfunction "VB0_14") (pintype "bidirectional"))
    )
    (net (code "58") (name "Net-(U7-VB1)") (class "Default")
      (node (ref "C7") (pin "1") (pinfunction "1_1") (pintype "passive"))
      (node (ref "U7") (pin "18") (pinfunction "VB1_18") (pintype "bidirectional"))
    )
    (net (code "59") (name "Net-(U7-VB2)") (class "Default")
      (node (ref "C8") (pin "1") (pinfunction "1_1") (pintype "passive"))
      (node (ref "U7") (pin "22") (pinfunction "VB2_22") (pintype "bidirectional"))
    )
    (net (code "60") (name "Net-(U7-VHV)") (class "Default")
      (node (ref "C2") (pin "2") (pinfunction "2_2") (pintype "passive"))
      (node (ref "R1") (pin "1") (pinfunction "1_1") (pintype "passive"))
      (node (ref "U7") (pin "35") (pinfunction "VHV_35") (pintype "power_in"))
    )
    (net (code "61") (name "Net-(U8-FB)") (class "Default")
      (node (ref "R56") (pin "2") (pinfunction "2_2") (pintype "passive"))
      (node (ref "R57") (pin "1") (pinfunction "1_1") (pintype "passive"))
      (node (ref "U8") (pin "4") (pinfunction "FB_4") (pintype "passive"))
    )
    (net (code "62") (name "Net-(U8-SW)") (class "Default")
      (node (ref "L2") (pin "1") (pinfunction "1_1") (pintype "passive"))
      (node (ref "U8") (pin "5") (pinfunction "SW_5") (pintype "passive"))
    )
    (net (code "63") (name "V3.3") (class "Default")
      (node (ref "C39") (pin "1") (pinfunction "1_1") (pintype "passive"))
      (node (ref "C5") (pin "1") (pinfunction "1_1") (pintype "passive"))
      (node (ref "P10") (pin "1") (pintype "passive"))
      (node (ref "P8") (pin "2") (pintype "passive"))
      (node (ref "R2") (pin "1") (pinfunction "1_1") (pintype "passive"))
      (node (ref "R24") (pin "1") (pinfunction "1_1") (pintype "passive"))
      (node (ref "R25") (pin "2") (pinfunction "2_2") (pintype "passive"))
      (node (ref "R27") (pin "1") (pinfunction "1_1") (pintype "passive"))
      (node (ref "R29") (pin "1") (pinfunction "1_1") (pintype "passive"))
      (node (ref "U7") (pin "34") (pinfunction "VDD33_34") (pintype "power_in"))
    )
    (net (code "64") (name "V5") (class "Default")
      (node (ref "C25") (pin "1") (pinfunction "1_1") (pintype "passive"))
      (node (ref "C26") (pin "1") (pinfunction "1_1") (pintype "passive"))
      (node (ref "C36") (pin "1") (pinfunction "1_1") (pintype "passive"))
      (node (ref "C37") (pin "1") (pinfunction "1_1") (pintype "passive"))
      (node (ref "L2") (pin "2") (pinfunction "2_2") (pintype "passive"))
      (node (ref "P2") (pin "5") (pinfunction "5_5") (pintype "passive"))
      (node (ref "R57") (pin "2") (pinfunction "2_2") (pintype "passive"))
      (node (ref "U3") (pin "3") (pinfunction "VIN_3") (pintype "passive"))
    )
    (net (code "65") (name "Vbus") (class "Default")
      (node (ref "C1") (pin "1") (pinfunction "1_1") (pintype "passive"))
      (node (ref "C15") (pin "1") (pinfunction "1_1") (pintype "passive"))
      (node (ref "C16") (pin "1") (pinfunction "1_1") (pintype "passive"))
      (node (ref "C17") (pin "1") (pinfunction "1_1") (pintype "passive"))
      (node (ref "C18") (pin "1") (pinfunction "1_1") (pintype "passive"))
      (node (ref "C19") (pin "1") (pinfunction "1_1") (pintype "passive"))
      (node (ref "C24") (pin "2") (pinfunction "2_2") (pintype "passive"))
      (node (ref "C34") (pin "1") (pinfunction "1_1") (pintype "passive"))
      (node (ref "C35") (pin "1") (pinfunction "1_1") (pintype "passive"))
      (node (ref "P1") (pin "1") (pintype "passive"))
      (node (ref "Q1") (pin "5") (pinfunction "D_5") (pintype "passive"))
      (node (ref "Q1") (pin "6") (pinfunction "D_6") (pintype "passive"))
      (node (ref "Q1") (pin "7") (pinfunction "D_7") (pintype "passive"))
      (node (ref "Q1") (pin "8") (pinfunction "D_8") (pintype "passive"))
      (node (ref "Q1") (pin "9") (pinfunction "D_9") (pintype "passive"))
      (node (ref "Q3") (pin "5") (pinfunction "D_5") (pintype "passive"))
      (node (ref "Q3") (pin "6") (pinfunction "D_6") (pintype "passive"))
      (node (ref "Q3") (pin "7") (pinfunction "D_7") (pintype "passive"))
      (node (ref "Q3") (pin "8") (pinfunction "D_8") (pintype "passive"))
      (node (ref "Q3") (pin "9") (pinfunction "D_9") (pintype "passive"))
      (node (ref "Q5") (pin "5") (pinfunction "D_5") (pintype "passive"))
      (node (ref "Q5") (pin "6") (pinfunction "D_6") (pintype "passive"))
      (node (ref "Q5") (pin "7") (pinfunction "D_7") (pintype "passive"))
      (node (ref "Q5") (pin "8") (pinfunction "D_8") (pintype "passive"))
      (node (ref "Q5") (pin "9") (pinfunction "D_9") (pintype "passive"))
      (node (ref "R1") (pin "2") (pinfunction "2_2") (pintype "passive"))
      (node (ref "R41") (pin "2") (pinfunction "2_2") (pintype "passive"))
      (node (ref "U8") (pin "1") (pinfunction "VIN_1") (pintype "passive"))
    )
    (net (code "66") (name "unconnected-(U7-PA0{slash}CC1{slash}A13-Pad37)") (class "Default")
      (node (ref "U7") (pin "37") (pinfunction "PA0/CC1/A13_37") (pintype "bidirectional"))
    )
    (net (code "67") (name "unconnected-(U7-PA7{slash}ISINK2{slash}CM3N2{slash}A2-Pad46)") (class "Default")
      (node (ref "U7") (pin "46") (pinfunction "PA7/ISINK2/CM3N2/A2_46") (pintype "bidirectional+no_connect"))
    )
    (net (code "68") (name "unconnected-(U7-PA12{slash}QII1{slash}A19-Pad3)") (class "Default")
      (node (ref "U7") (pin "3") (pinfunction "PA12/QII1/A19_3") (pintype "bidirectional"))
    )
    (net (code "69") (name "unconnected-(U7-PA15{slash}T1BK{slash}Q_DET2{slash}A10-Pad6)") (class "Default")
      (node (ref "U7") (pin "6") (pinfunction "PA15/T1BK/Q_DET2/A10_6") (pintype "bidirectional"))
    )
    (net (code "70") (name "unconnected-(U7-PB14{slash}LO3-Pad24)") (class "Default")
      (node (ref "U7") (pin "24") (pinfunction "PB14/LO3_24") (pintype "bidirectional"))
    )
    (net (code "71") (name "unconnected-(U7-PB15{slash}T1C4_{slash}HO3-Pad27)") (class "Default")
      (node (ref "U7") (pin "27") (pinfunction "PB15/T1C4_/HO3_27") (pintype "output"))
    )
    (net (code "72") (name "unconnected-(U7-VB3-Pad26)") (class "Default")
      (node (ref "U7") (pin "26") (pinfunction "VB3_26") (pintype "bidirectional"))
    )
    (net (code "73") (name "unconnected-(U7-VS3-Pad25)") (class "Default")
      (node (ref "U7") (pin "25") (pinfunction "VS3_25") (pintype "bidirectional"))
    )
    (net (code "74") (name "unconnected-(U8-EN-Pad3)") (class "Default")
      (node (ref "U8") (pin "3") (pinfunction "EN_3") (pintype "passive"))
    )
  )
)
